# Charging_1AOut3.net
KiCad netlist of a schematic drawn in Altium Designer
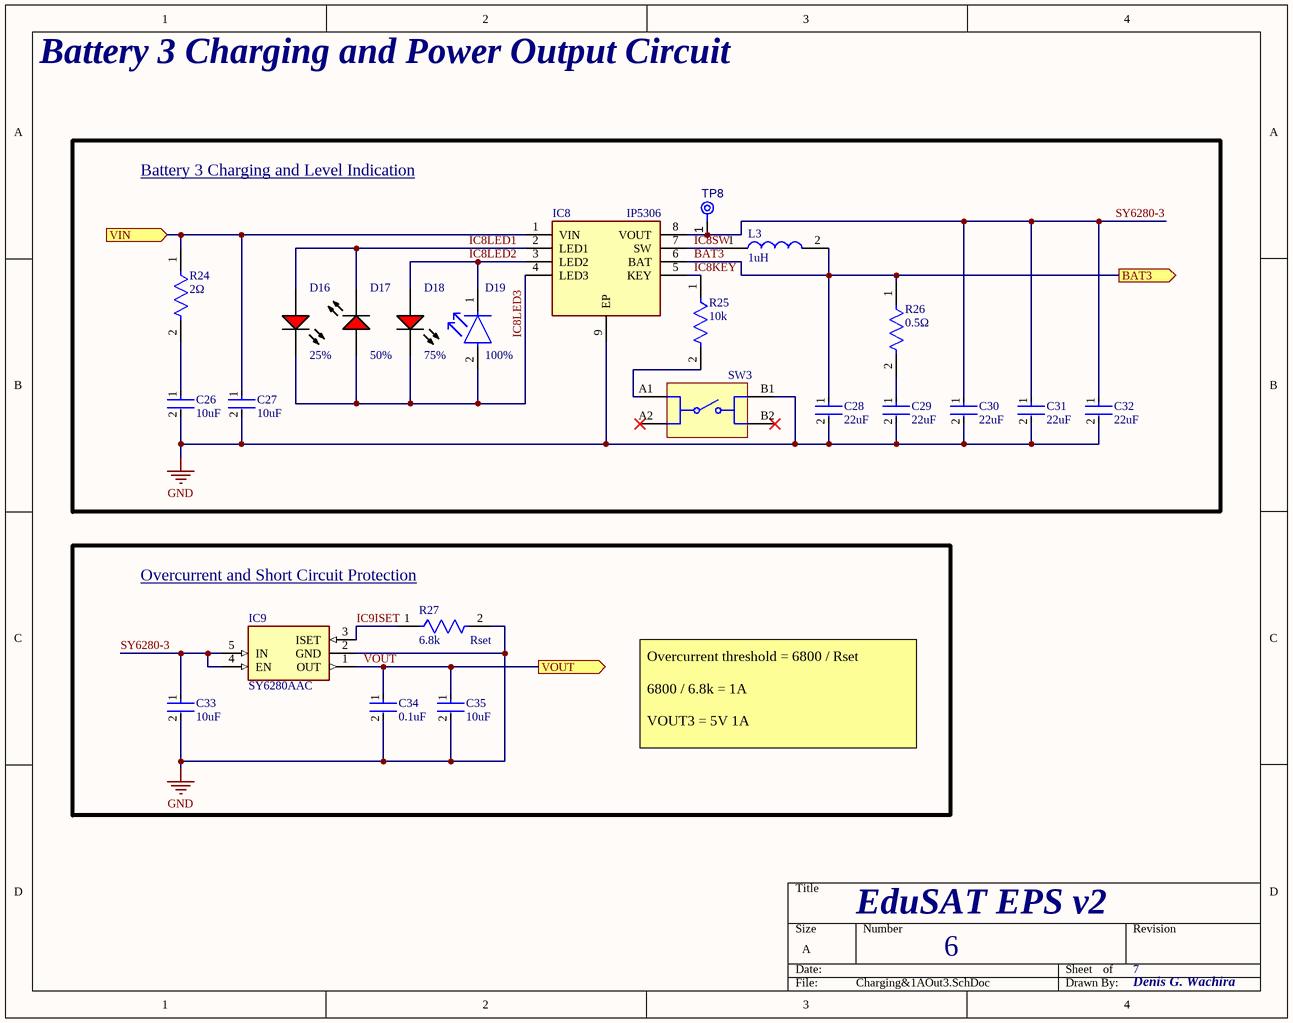
[diagram p0: Charging&1AOut3.SchDoc]

(export (version "E")
  (design (tool "Eeschema 10.0.6"))
  (components
    (comp (ref "C26")
      (value "10uF")
      (footprint "FP-CL21-IPC_A")
      (description "CL21 Series 0805 10uF 25V ±10% Tolerance X5R Multilayer Ceramic Chip Capacitor CL21A106KAYNNNE")
      (fields (field (name "TOLERANCE") "10%"))
      (libsource (lib "Altium Content Vault") (part "b4654b650e69147ec39a6b967a45e02"))
    )
    (comp (ref "C27")
      (value "10uF")
      (footprint "FP-CL21-IPC_A")
      (description "CL21 Series 0805 10uF 25V ±10% Tolerance X5R Multilayer Ceramic Chip Capacitor CL21A106KAYNNNE")
      (fields (field (name "TOLERANCE") "10%"))
      (libsource (lib "Altium Content Vault") (part "b4654b650e69147ec39a6b967a45e02"))
    )
    (comp (ref "C28")
      (value "22uF")
      (footprint "FP-CL21-IPC_C")
      (description "CL21 Series 0805 22uF 25V ±20% Tolerance X5R Multilayer Ceramic Chip Capacitor CL21A226MAYNNNE")
      (libsource (lib "Altium Content Vault") (part "b4654b650e69147ec39a6b967a45e02"))
    )
    (comp (ref "C29")
      (value "22uF")
      (footprint "FP-CL21-IPC_C")
      (description "CL21 Series 0805 22uF 25V ±20% Tolerance X5R Multilayer Ceramic Chip Capacitor CL21A226MAYNNNE")
      (libsource (lib "Altium Content Vault") (part "b4654b650e69147ec39a6b967a45e02"))
    )
    (comp (ref "C30")
      (value "22uF")
      (footprint "FP-CL21-IPC_C")
      (description "CL21 Series 0805 22uF 25V ±20% Tolerance X5R Multilayer Ceramic Chip Capacitor CL21A226MAYNNNE")
      (libsource (lib "Altium Content Vault") (part "b4654b650e69147ec39a6b967a45e02"))
    )
    (comp (ref "C31")
      (value "22uF")
      (footprint "FP-CL21-IPC_C")
      (description "CL21 Series 0805 22uF 25V ±20% Tolerance X5R Multilayer Ceramic Chip Capacitor CL21A226MAYNNNE")
      (libsource (lib "Altium Content Vault") (part "b4654b650e69147ec39a6b967a45e02"))
    )
    (comp (ref "C32")
      (value "22uF")
      (footprint "FP-CL21-IPC_C")
      (description "CL21 Series 0805 22uF 25V ±20% Tolerance X5R Multilayer Ceramic Chip Capacitor CL21A226MAYNNNE")
      (libsource (lib "Altium Content Vault") (part "b4654b650e69147ec39a6b967a45e02"))
    )
    (comp (ref "C33")
      (value "10uF")
      (footprint "FP-CL21-IPC_A")
      (description "CL21 Series 0805 10uF 25V ±10% Tolerance X5R Multilayer Ceramic Chip Capacitor CL21A106KAYNNNE")
      (fields (field (name "TOLERANCE") "10%"))
      (libsource (lib "Altium Content Vault") (part "b4654b650e69147ec39a6b967a45e02"))
    )
    (comp (ref "C34")
      (value "0.1uF")
      (footprint "FP-CL21-IPC_A")
      (description "50V 0.1uF X7R ±10% 0805 Multilayer Ceramic Capacitors MLCC - SMD/SMT ROHS TCC0805X7R104K500DT")
      (fields (field (name "TOLERANCE") "10%"))
      (libsource (lib "Altium Content Vault") (part "b4654b650e69147ec39a6b967a45e02"))
    )
    (comp (ref "C35")
      (value "10uF")
      (footprint "FP-CL21-IPC_A")
      (description "CL21 Series 0805 10uF 25V ±10% Tolerance X5R Multilayer Ceramic Chip Capacitor CL21A106KAYNNNE")
      (fields (field (name "TOLERANCE") "10%"))
      (libsource (lib "Altium Content Vault") (part "b4654b650e69147ec39a6b967a45e02"))
    )
    (comp (ref "D16")
      (value "25%")
      (footprint "LTST-C170KRKT_V")
      (description "LED Red,KT-0805R")
      (fields (field (name "MANUFACTURER") "Lite-On"))
      (libsource (lib "Altium Content Vault") (part "LED-RED-AK-2"))
    )
    (comp (ref "D17")
      (value "50%")
      (footprint "LTST-C170KRKT_V")
      (description "LED Red, KT-0805R")
      (fields (field (name "MANUFACTURER") "Lite-On"))
      (libsource (lib "Altium Content Vault") (part "LED-RED-AK-2"))
    )
    (comp (ref "D18")
      (value "75%")
      (footprint "LTST-C170KRKT_V")
      (description "LED Red, KT-0805R")
      (fields (field (name "MANUFACTURER") "Lite-On"))
      (libsource (lib "Altium Content Vault") (part "LED-RED-AK-2"))
    )
    (comp (ref "D19")
      (value "100%")
      (footprint "FP-LTST-C170GKT-MFG")
      (description "LED GREEN CLEAR SMD KT-0805G")
      (fields (field (name "VOLTAGE") "5V"))
      (libsource (lib "Altium Content Vault") (part "8706943c75ba83719d021d2fdc84c58"))
    )
    (comp (ref "IC8")
      (value "IP5306")
      (footprint "SamacSys:SOIC127P600X165-9N")
      (description "Integrated Circuit")
      (libsource (lib "IP5306") (part "IP5306"))
    )
    (comp (ref "IC9")
      (value "SY6280AAC")
      (footprint "SamacSys:SOT95P285X140-5N")
      (description "Integrated Circuit")
      (libsource (lib "*") (part "SY6280AAC"))
    )
    (comp (ref "L3")
      (value "1uH")
      (footprint "SamacSys:INDPM7366X300N")
      (description "Inductor MCS0630-1R0MN2")
      (fields (field (name "MANUFACTURER_PART_NUMBER") "MCS0630-1R0MN2"))
      (libsource (lib "*") (part "MCS0630-2R2MN2"))
    )
    (comp (ref "R24")
      (value "2Ω")
      (footprint "FP-CR0805-IPC_B")
      (description "Thick Film Chip Resistors 0805 2Ω 0.125W 1% 250ppm/°C \r\nRS-05L2R00FT")
      (fields (field (name "TOLERANCE") "1%"))
      (libsource (lib "Altium Content Vault") (part "1029c3af85768c4190bb7ad29bc67b5"))
    )
    (comp (ref "R25")
      (value "10k")
      (footprint "FP-MCR10-IPC_C")
      (description "Thick Film Chip Resistor, 0805, 10kΩ, 1%, 100ppm/°C, 0.125W, 150V \r\n0805W8F1002T5E")
      (fields (field (name "TOLERANCE") "1%"))
      (libsource (lib "Altium Content Vault") (part "1029c3af85768c4190bb7ad29bc67b5"))
    )
    (comp (ref "R26")
      (value "0.5Ω")
      (footprint "FP-MCR10-IPC_C")
      (description "Thick Film Chip Resistor, 0805, 0.5R, 1%, 100ppm/°C, 0.125W, 150V \r\n0805W8F500LT5E")
      (fields (field (name "TOLERANCE") "1%"))
      (libsource (lib "Altium Content Vault") (part "1029c3af85768c4190bb7ad29bc67b5"))
    )
    (comp (ref "R27")
      (value "6.8k          Rset")
      (footprint "FP-MCR10-IPC_C")
      (description "Thick Film Chip Resistor, 0805, 6.8kΩ, 1%, 100ppm/°C, 0.125W, 150V \r\n0805W8F6801T5E")
      (fields (field (name "TOLERANCE") "1%"))
      (libsource (lib "Altium Content Vault") (part "1029c3af85768c4190bb7ad29bc67b5"))
    )
    (comp (ref "SW3")
      (value "430181038816")
      (footprint "WS-TASV_L4.5W4.5H3.8_430181038816")
      (libsource (lib "Altium Content Vault") (part "SPST-NO_4P"))
    )
    (comp (ref "TP8")
      (value "TPAD6R")
      (footprint "TP06R")
      (description "0.6mm round")
      (libsource (lib "University of Nairobi") (part "CMP-001-0001-4"))
    )
  )
  (nets
    (net (code "1") (name "/BAT3") (class "Default")
      (node (ref "C28") (pin "1") (pinfunction "1_1") (pintype "passive"))
      (node (ref "IC8") (pin "6") (pinfunction "BAT_6") (pintype "passive"))
      (node (ref "L3") (pin "2") (pinfunction "2_2") (pintype "passive"))
      (node (ref "R26") (pin "1") (pinfunction "1_1") (pintype "passive"))
    )
    (net (code "2") (name "/IC8KEY") (class "Default")
      (node (ref "IC8") (pin "5") (pinfunction "KEY_5") (pintype "passive"))
      (node (ref "R25") (pin "1") (pinfunction "1_1") (pintype "passive"))
    )
    (net (code "3") (name "/IC8LED1") (class "Default")
      (node (ref "D16") (pin "1") (pinfunction "A_1") (pintype "passive"))
      (node (ref "D17") (pin "2") (pinfunction "K_2") (pintype "passive"))
      (node (ref "IC8") (pin "2") (pinfunction "LED1_2") (pintype "passive"))
    )
    (net (code "4") (name "/IC8LED2") (class "Default")
      (node (ref "D18") (pin "1") (pinfunction "A_1") (pintype "passive"))
      (node (ref "D19") (pin "1") (pinfunction "C_1") (pintype "passive"))
      (node (ref "IC8") (pin "3") (pinfunction "LED2_3") (pintype "passive"))
    )
    (net (code "5") (name "/IC8LED3") (class "Default")
      (node (ref "D16") (pin "2") (pinfunction "K_2") (pintype "passive"))
      (node (ref "D17") (pin "1") (pinfunction "A_1") (pintype "passive"))
      (node (ref "D18") (pin "2") (pinfunction "K_2") (pintype "passive"))
      (node (ref "D19") (pin "2") (pinfunction "A_2") (pintype "passive"))
      (node (ref "IC8") (pin "4") (pinfunction "LED3_4") (pintype "passive"))
    )
    (net (code "6") (name "/IC8SW") (class "Default")
      (node (ref "IC8") (pin "7") (pinfunction "SW_7") (pintype "passive"))
      (node (ref "L3") (pin "1") (pinfunction "1_1") (pintype "passive"))
    )
    (net (code "7") (name "/IC9ISET") (class "Default")
      (node (ref "IC9") (pin "3") (pinfunction "ISET_3") (pintype "input"))
      (node (ref "R27") (pin "1") (pinfunction "1_1") (pintype "passive"))
    )
    (net (code "8") (name "/SY6280-3") (class "Default")
      (node (ref "C30") (pin "1") (pinfunction "1_1") (pintype "passive"))
      (node (ref "C31") (pin "1") (pinfunction "1_1") (pintype "passive"))
      (node (ref "C32") (pin "1") (pinfunction "1_1") (pintype "passive"))
      (node (ref "C33") (pin "1") (pinfunction "1_1") (pintype "passive"))
      (node (ref "IC8") (pin "8") (pinfunction "VOUT_8") (pintype "passive"))
      (node (ref "IC9") (pin "4") (pinfunction "EN_4") (pintype "input"))
      (node (ref "IC9") (pin "5") (pinfunction "IN_5") (pintype "input"))
      (node (ref "TP8") (pin "1") (pinfunction "TP_1") (pintype "passive"))
    )
    (net (code "9") (name "/VIN") (class "Default")
      (node (ref "C27") (pin "1") (pinfunction "1_1") (pintype "passive"))
      (node (ref "IC8") (pin "1") (pinfunction "VIN_1") (pintype "passive"))
      (node (ref "R24") (pin "1") (pinfunction "1_1") (pintype "passive"))
    )
    (net (code "10") (name "/VOUT") (class "Default")
      (node (ref "C34") (pin "1") (pinfunction "1_1") (pintype "passive"))
      (node (ref "C35") (pin "1") (pinfunction "1_1") (pintype "passive"))
      (node (ref "IC9") (pin "1") (pinfunction "OUT_1") (pintype "output"))
    )
    (net (code "11") (name "GND") (class "Default")
      (node (ref "C26") (pin "2") (pinfunction "2_2") (pintype "passive"))
      (node (ref "C27") (pin "2") (pinfunction "2_2") (pintype "passive"))
      (node (ref "C28") (pin "2") (pinfunction "2_2") (pintype "passive"))
      (node (ref "C29") (pin "2") (pinfunction "2_2") (pintype "passive"))
      (node (ref "C30") (pin "2") (pinfunction "2_2") (pintype "passive"))
      (node (ref "C31") (pin "2") (pinfunction "2_2") (pintype "passive"))
      (node (ref "C32") (pin "2") (pinfunction "2_2") (pintype "passive"))
      (node (ref "C33") (pin "2") (pinfunction "2_2") (pintype "passive"))
      (node (ref "C34") (pin "2") (pinfunction "2_2") (pintype "passive"))
      (node (ref "C35") (pin "2") (pinfunction "2_2") (pintype "passive"))
      (node (ref "IC8") (pin "9") (pinfunction "EP_9") (pintype "passive"))
      (node (ref "IC9") (pin "2") (pinfunction "GND_2") (pintype "power_in"))
      (node (ref "R27") (pin "2") (pinfunction "2_2") (pintype "passive"))
      (node (ref "SW3") (pin "B1") (pinfunction "B1_B1") (pintype "passive"))
    )
    (net (code "12") (name "Net-(C26-Pad1)") (class "Default")
      (node (ref "C26") (pin "1") (pinfunction "1_1") (pintype "passive"))
      (node (ref "R24") (pin "2") (pinfunction "2_2") (pintype "passive"))
    )
    (net (code "13") (name "Net-(C29-Pad1)") (class "Default")
      (node (ref "C29") (pin "1") (pinfunction "1_1") (pintype "passive"))
      (node (ref "R26") (pin "2") (pinfunction "2_2") (pintype "passive"))
    )
    (net (code "14") (name "Net-(R25-Pad2)") (class "Default")
      (node (ref "R25") (pin "2") (pinfunction "2_2") (pintype "passive"))
      (node (ref "SW3") (pin "A1") (pinfunction "A1_A1") (pintype "passive"))
    )
    (net (code "15") (name "unconnected-(SW3-PadA2)") (class "Default")
      (node (ref "SW3") (pin "A2") (pinfunction "A2_A2") (pintype "passive+no_connect"))
    )
    (net (code "16") (name "unconnected-(SW3-PadB2)") (class "Default")
      (node (ref "SW3") (pin "B2") (pinfunction "B2_B2") (pintype "passive+no_connect"))
    )
  )
)
